# DAC_GainOutputStage.net
KiCad netlist of a schematic drawn in EAGLE
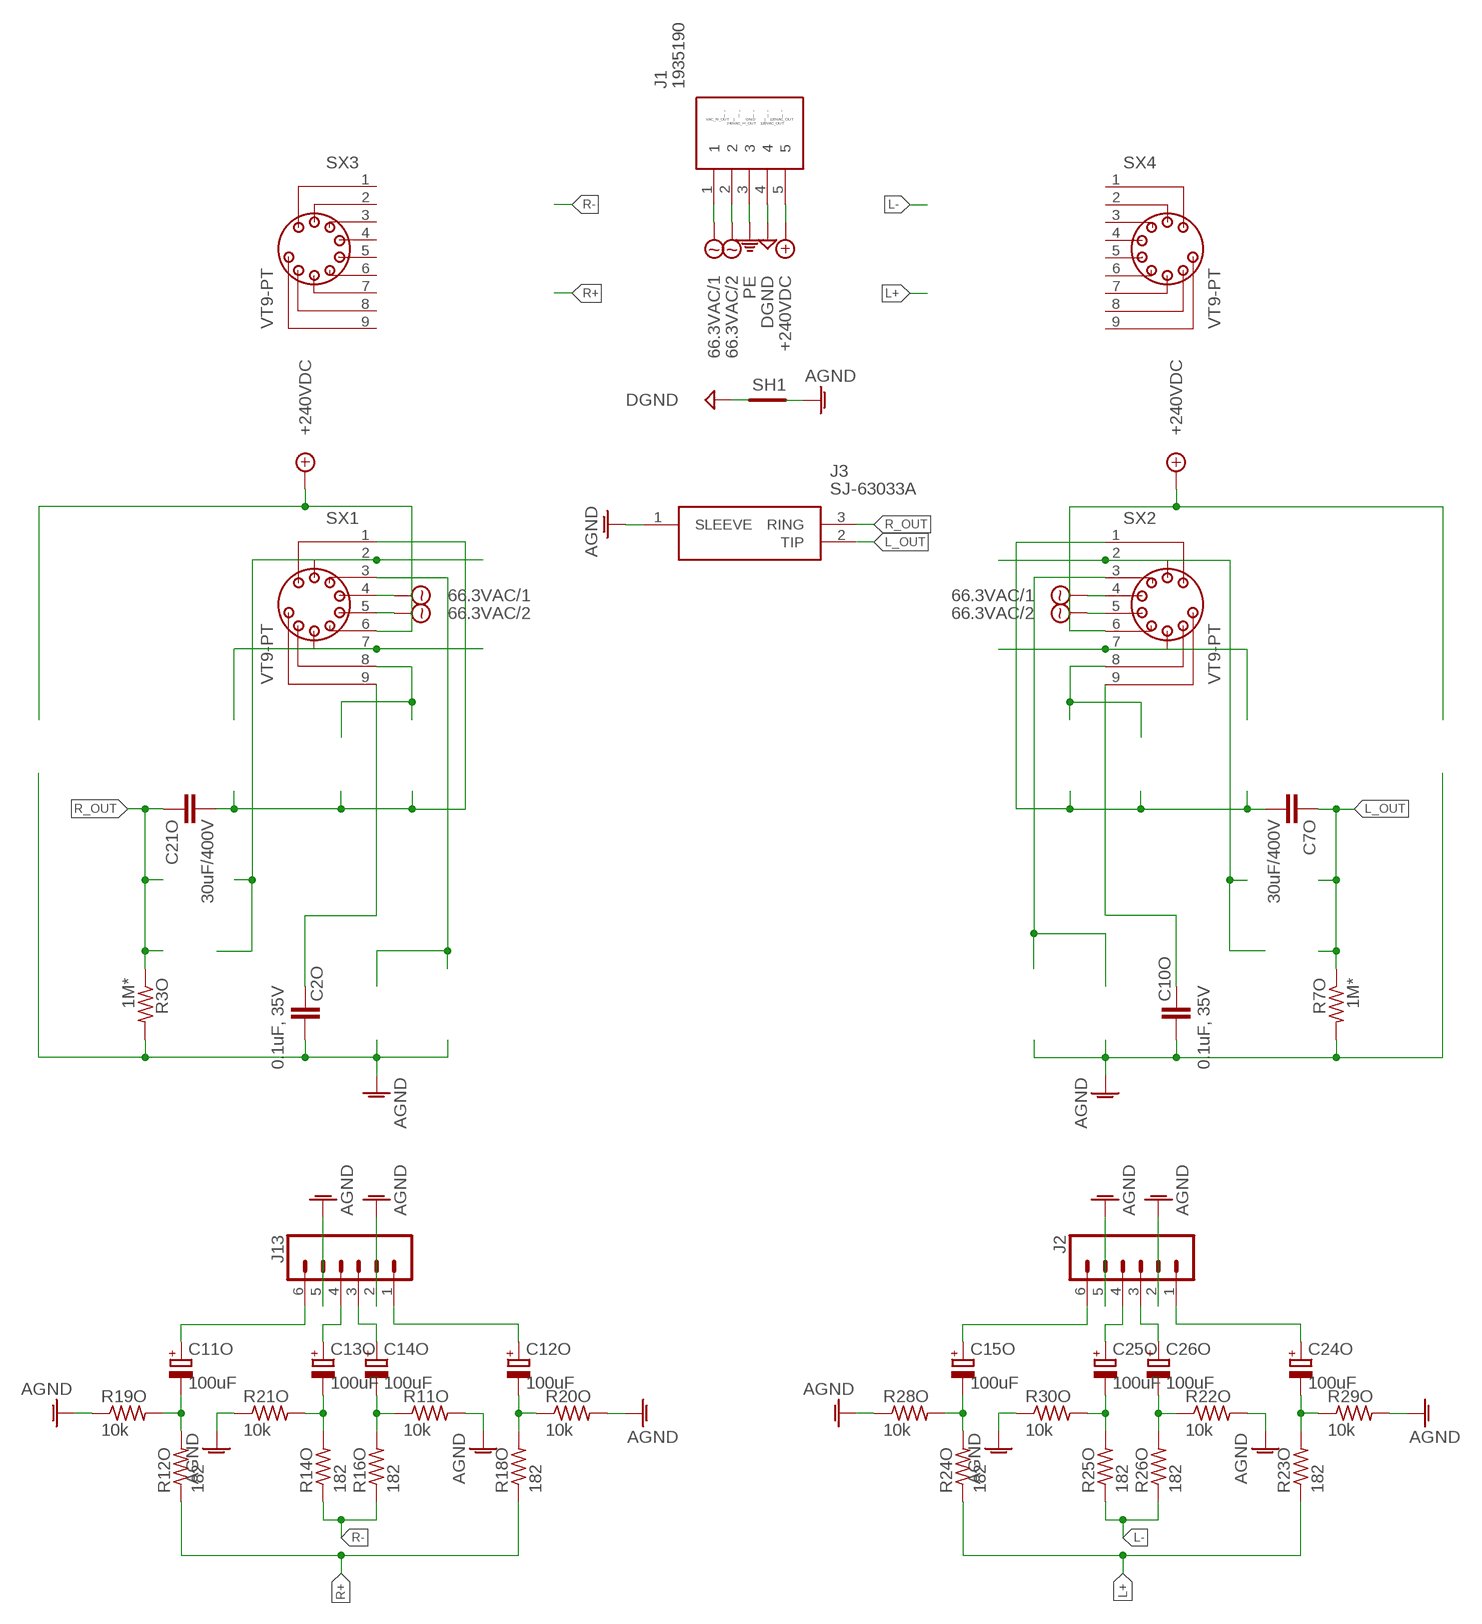
[diagram p0: schematic, sheet 1]

(export (version "E")
  (design (tool "Eeschema 10.0.6"))
  (components
    (comp (ref "C2O")
      (value "0.1uF, 35V")
      (footprint "eagle-import:MKS4B031002A00JC00")
      (fields
        (field (name "MANUFACTURER_PART_NUMBER") "MKS4B031002A00JC00")
        (field (name "MOUSER_PART_NUMBER") "505-MKS4B0312AJC")
      )
      (libsource (lib "eagle-import") (part "MKS4B031002A00JC00"))
    )
    (comp (ref "C7O")
      (value "30uF/400V")
      (footprint "eagle-import:DCP4G053006ID2KSSD")
      (fields
        (field (name "MANUFACTURER_PART_NUMBER") "DCP4G053006ID2KSSD")
        (field (name "MOUSER_PART_NUMBER") "505-DCP4G0536ID2KSSD")
      )
      (libsource (lib "eagle-import") (part "DCP4G053006ID2KSSD"))
    )
    (comp (ref "C10O")
      (value "0.1uF, 35V")
      (footprint "eagle-import:MKS4B031002A00JC00")
      (fields
        (field (name "MANUFACTURER_PART_NUMBER") "MKS4B031002A00JC00")
        (field (name "MOUSER_PART_NUMBER") "505-MKS4B0312AJC")
      )
      (libsource (lib "eagle-import") (part "MKS4B031002A00JC00"))
    )
    (comp (ref "C11O")
      (value "100uF")
      (footprint "eagle-import:CAPPRD350W60D825H1300")
      (fields
        (field (name "ARROW_PART_NUMBER") "UFW1H101MPD1TD")
        (field (name "MOUSER_PART_NUMBER") "647-UFW1H101MPD1TD")
      )
      (libsource (lib "eagle-import") (part "UFW1H101MPD1TD"))
    )
    (comp (ref "C12O")
      (value "100uF")
      (footprint "eagle-import:CAPPRD350W60D825H1300")
      (fields
        (field (name "ARROW_PART_NUMBER") "UFW1H101MPD1TD")
        (field (name "MOUSER_PART_NUMBER") "647-UFW1H101MPD1TD")
      )
      (libsource (lib "eagle-import") (part "UFW1H101MPD1TD"))
    )
    (comp (ref "C13O")
      (value "100uF")
      (footprint "eagle-import:CAPPRD350W60D825H1300")
      (fields
        (field (name "ARROW_PART_NUMBER") "UFW1H101MPD1TD")
        (field (name "MOUSER_PART_NUMBER") "647-UFW1H101MPD1TD")
      )
      (libsource (lib "eagle-import") (part "UFW1H101MPD1TD"))
    )
    (comp (ref "C14O")
      (value "100uF")
      (footprint "eagle-import:CAPPRD350W60D825H1300")
      (fields
        (field (name "ARROW_PART_NUMBER") "UFW1H101MPD1TD")
        (field (name "MOUSER_PART_NUMBER") "647-UFW1H101MPD1TD")
      )
      (libsource (lib "eagle-import") (part "UFW1H101MPD1TD"))
    )
    (comp (ref "C15O")
      (value "100uF")
      (footprint "eagle-import:CAPPRD350W60D825H1300")
      (fields
        (field (name "ARROW_PART_NUMBER") "UFW1H101MPD1TD")
        (field (name "MOUSER_PART_NUMBER") "647-UFW1H101MPD1TD")
      )
      (libsource (lib "eagle-import") (part "UFW1H101MPD1TD"))
    )
    (comp (ref "C21O")
      (value "30uF/400V")
      (footprint "eagle-import:DCP4G053006ID2KSSD")
      (fields
        (field (name "MANUFACTURER_PART_NUMBER") "DCP4G053006ID2KSSD")
        (field (name "MOUSER_PART_NUMBER") "505-DCP4G0536ID2KSSD")
      )
      (libsource (lib "eagle-import") (part "DCP4G053006ID2KSSD"))
    )
    (comp (ref "C24O")
      (value "100uF")
      (footprint "eagle-import:CAPPRD350W60D825H1300")
      (fields
        (field (name "ARROW_PART_NUMBER") "UFW1H101MPD1TD")
        (field (name "MOUSER_PART_NUMBER") "647-UFW1H101MPD1TD")
      )
      (libsource (lib "eagle-import") (part "UFW1H101MPD1TD"))
    )
    (comp (ref "C25O")
      (value "100uF")
      (footprint "eagle-import:CAPPRD350W60D825H1300")
      (fields
        (field (name "ARROW_PART_NUMBER") "UFW1H101MPD1TD")
        (field (name "MOUSER_PART_NUMBER") "647-UFW1H101MPD1TD")
      )
      (libsource (lib "eagle-import") (part "UFW1H101MPD1TD"))
    )
    (comp (ref "C26O")
      (value "100uF")
      (footprint "eagle-import:CAPPRD350W60D825H1300")
      (fields
        (field (name "ARROW_PART_NUMBER") "UFW1H101MPD1TD")
        (field (name "MOUSER_PART_NUMBER") "647-UFW1H101MPD1TD")
      )
      (libsource (lib "eagle-import") (part "UFW1H101MPD1TD"))
    )
    (comp (ref "J1")
      (value "1935190")
      (footprint "eagle-import:1935190")
      (fields (field (name "MOUSER_PART_NUMBER") "651-1935190"))
      (libsource (lib "eagle-import") (part "1935190"))
    )
    (comp (ref "J2")
      (value "CONN_06SILK_FEMALE_PTH")
      (footprint "eagle-import:1X06")
      (libsource (lib "eagle-import") (part "CONN_06SILK_FEMALE_PTH"))
    )
    (comp (ref "J3")
      (value "SJ-63033A")
      (footprint "eagle-import:SJ63033A")
      (libsource (lib "eagle-import") (part "SJ-63033A"))
    )
    (comp (ref "J13")
      (value "CONN_06SILK_FEMALE_PTH")
      (footprint "eagle-import:1X06")
      (libsource (lib "eagle-import") (part "CONN_06SILK_FEMALE_PTH"))
    )
    (comp (ref "R3O")
      (value "1M*")
      (footprint "eagle-import:RESAD1540W60L620D230")
      (fields
        (field (name "MANUFACTURER_PART_NUMBER") "LR1F1M0")
        (field (name "MOUSER_PART_NUMBER") "279-LR1F1M0")
      )
      (libsource (lib "eagle-import") (part "LR1F1M0"))
    )
    (comp (ref "R7O")
      (value "1M*")
      (footprint "eagle-import:RESAD1540W60L620D230")
      (fields
        (field (name "MANUFACTURER_PART_NUMBER") "LR1F1M0")
        (field (name "MOUSER_PART_NUMBER") "279-LR1F1M0")
      )
      (libsource (lib "eagle-import") (part "LR1F1M0"))
    )
    (comp (ref "R11O")
      (value "10k")
      (footprint "eagle-import:RESAD1540W55L620D230")
      (fields
        (field (name "MANUFACTURER_PART_NUMBER") "LR1F10K")
        (field (name "MOUSER_PART_NUMBER") "279-LR1F10K")
      )
      (libsource (lib "eagle-import") (part "LR1F10K"))
    )
    (comp (ref "R12O")
      (value "182")
      (footprint "eagle-import:RESAD1590W60L630D240")
      (fields (field (name "MANUFACTURER_PART_NUMBER") "MF0207FTE52-182R"))
      (libsource (lib "eagle-import") (part "MF0207FTE52-182R"))
    )
    (comp (ref "R14O")
      (value "182")
      (footprint "eagle-import:RESAD1590W60L630D240")
      (fields (field (name "MANUFACTURER_PART_NUMBER") "MF0207FTE52-182R"))
      (libsource (lib "eagle-import") (part "MF0207FTE52-182R"))
    )
    (comp (ref "R16O")
      (value "182")
      (footprint "eagle-import:RESAD1590W60L630D240")
      (fields (field (name "MANUFACTURER_PART_NUMBER") "MF0207FTE52-182R"))
      (libsource (lib "eagle-import") (part "MF0207FTE52-182R"))
    )
    (comp (ref "R18O")
      (value "182")
      (footprint "eagle-import:RESAD1590W60L630D240")
      (fields (field (name "MANUFACTURER_PART_NUMBER") "MF0207FTE52-182R"))
      (libsource (lib "eagle-import") (part "MF0207FTE52-182R"))
    )
    (comp (ref "R19O")
      (value "10k")
      (footprint "eagle-import:RESAD1540W55L620D230")
      (fields
        (field (name "MANUFACTURER_PART_NUMBER") "LR1F10K")
        (field (name "MOUSER_PART_NUMBER") "279-LR1F10K")
      )
      (libsource (lib "eagle-import") (part "LR1F10K"))
    )
    (comp (ref "R20O")
      (value "10k")
      (footprint "eagle-import:RESAD1540W55L620D230")
      (fields
        (field (name "MANUFACTURER_PART_NUMBER") "LR1F10K")
        (field (name "MOUSER_PART_NUMBER") "279-LR1F10K")
      )
      (libsource (lib "eagle-import") (part "LR1F10K"))
    )
    (comp (ref "R21O")
      (value "10k")
      (footprint "eagle-import:RESAD1540W55L620D230")
      (fields
        (field (name "MANUFACTURER_PART_NUMBER") "LR1F10K")
        (field (name "MOUSER_PART_NUMBER") "279-LR1F10K")
      )
      (libsource (lib "eagle-import") (part "LR1F10K"))
    )
    (comp (ref "R22O")
      (value "10k")
      (footprint "eagle-import:RESAD1540W55L620D230")
      (fields
        (field (name "MANUFACTURER_PART_NUMBER") "LR1F10K")
        (field (name "MOUSER_PART_NUMBER") "279-LR1F10K")
      )
      (libsource (lib "eagle-import") (part "LR1F10K"))
    )
    (comp (ref "R23O")
      (value "182")
      (footprint "eagle-import:RESAD1590W60L630D240")
      (fields (field (name "MANUFACTURER_PART_NUMBER") "MF0207FTE52-182R"))
      (libsource (lib "eagle-import") (part "MF0207FTE52-182R"))
    )
    (comp (ref "R24O")
      (value "182")
      (footprint "eagle-import:RESAD1590W60L630D240")
      (fields (field (name "MANUFACTURER_PART_NUMBER") "MF0207FTE52-182R"))
      (libsource (lib "eagle-import") (part "MF0207FTE52-182R"))
    )
    (comp (ref "R25O")
      (value "182")
      (footprint "eagle-import:RESAD1590W60L630D240")
      (fields (field (name "MANUFACTURER_PART_NUMBER") "MF0207FTE52-182R"))
      (libsource (lib "eagle-import") (part "MF0207FTE52-182R"))
    )
    (comp (ref "R26O")
      (value "182")
      (footprint "eagle-import:RESAD1590W60L630D240")
      (fields (field (name "MANUFACTURER_PART_NUMBER") "MF0207FTE52-182R"))
      (libsource (lib "eagle-import") (part "MF0207FTE52-182R"))
    )
    (comp (ref "R28O")
      (value "10k")
      (footprint "eagle-import:RESAD1540W55L620D230")
      (fields
        (field (name "MANUFACTURER_PART_NUMBER") "LR1F10K")
        (field (name "MOUSER_PART_NUMBER") "279-LR1F10K")
      )
      (libsource (lib "eagle-import") (part "LR1F10K"))
    )
    (comp (ref "R29O")
      (value "10k")
      (footprint "eagle-import:RESAD1540W55L620D230")
      (fields
        (field (name "MANUFACTURER_PART_NUMBER") "LR1F10K")
        (field (name "MOUSER_PART_NUMBER") "279-LR1F10K")
      )
      (libsource (lib "eagle-import") (part "LR1F10K"))
    )
    (comp (ref "R30O")
      (value "10k")
      (footprint "eagle-import:RESAD1540W55L620D230")
      (fields
        (field (name "MANUFACTURER_PART_NUMBER") "LR1F10K")
        (field (name "MOUSER_PART_NUMBER") "279-LR1F10K")
      )
      (libsource (lib "eagle-import") (part "LR1F10K"))
    )
    (comp (ref "SH1")
      (value "SHORTA5")
      (footprint "eagle-import:SHORT_ALL-50")
      (libsource (lib "eagle-import") (part "SHORTA5"))
    )
    (comp (ref "SX1")
      (value "VT9-PT")
      (footprint "eagle-import:VT9-PT")
      (libsource (lib "eagle-import") (part "VT9-PT"))
    )
    (comp (ref "SX2")
      (value "VT9-PT")
      (footprint "eagle-import:VT9-PT")
      (libsource (lib "eagle-import") (part "VT9-PT"))
    )
    (comp (ref "SX3")
      (value "VT9-PT")
      (footprint "eagle-import:VT9-PT")
      (libsource (lib "eagle-import") (part "VT9-PT"))
    )
    (comp (ref "SX4")
      (value "VT9-PT")
      (footprint "eagle-import:VT9-PT")
      (libsource (lib "eagle-import") (part "VT9-PT"))
    )
  )
  (nets
    (net (code "1") (name "+240VDC") (class "Default")
      (node (ref "J1") (pin "5") (pinfunction "5_5") (pintype "bidirectional"))
      (node (ref "SX1") (pin "6") (pinfunction "6_6") (pintype "passive"))
      (node (ref "SX2") (pin "6") (pinfunction "6_6") (pintype "passive"))
    )
    (net (code "2") (name "66.3VAC{slash}1") (class "Default")
      (node (ref "J1") (pin "1") (pinfunction "1_1") (pintype "bidirectional"))
      (node (ref "SX1") (pin "4") (pinfunction "4_4") (pintype "passive"))
      (node (ref "SX2") (pin "4") (pinfunction "4_4") (pintype "passive"))
    )
    (net (code "3") (name "66.3VAC{slash}2") (class "Default")
      (node (ref "J1") (pin "2") (pinfunction "2_2") (pintype "bidirectional"))
      (node (ref "SX1") (pin "5") (pinfunction "5_5") (pintype "passive"))
      (node (ref "SX2") (pin "5") (pinfunction "5_5") (pintype "passive"))
    )
    (net (code "4") (name "AGND") (class "Default")
      (node (ref "C10O") (pin "2") (pinfunction "2_2") (pintype "passive"))
      (node (ref "C2O") (pin "2") (pinfunction "2_2") (pintype "passive"))
      (node (ref "J13") (pin "2") (pinfunction "2_2") (pintype "passive"))
      (node (ref "J13") (pin "5") (pinfunction "5_5") (pintype "passive"))
      (node (ref "J2") (pin "2") (pinfunction "2_2") (pintype "passive"))
      (node (ref "J2") (pin "5") (pinfunction "5_5") (pintype "passive"))
      (node (ref "J3") (pin "1") (pinfunction "SLEEVE_1") (pintype "bidirectional"))
      (node (ref "R11O") (pin "2") (pinfunction "2_2") (pintype "passive"))
      (node (ref "R19O") (pin "1") (pinfunction "1_1") (pintype "passive"))
      (node (ref "R20O") (pin "2") (pinfunction "2_2") (pintype "passive"))
      (node (ref "R21O") (pin "1") (pinfunction "1_1") (pintype "passive"))
      (node (ref "R22O") (pin "2") (pinfunction "2_2") (pintype "passive"))
      (node (ref "R28O") (pin "1") (pinfunction "1_1") (pintype "passive"))
      (node (ref "R29O") (pin "2") (pinfunction "2_2") (pintype "passive"))
      (node (ref "R30O") (pin "1") (pinfunction "1_1") (pintype "passive"))
      (node (ref "R3O") (pin "2") (pinfunction "2_2") (pintype "passive"))
      (node (ref "R7O") (pin "2") (pinfunction "2_2") (pintype "passive"))
      (node (ref "SH1") (pin "2") (pinfunction "P$2_2") (pintype "bidirectional"))
    )
    (net (code "5") (name "DGND") (class "Default")
      (node (ref "J1") (pin "4") (pinfunction "4_4") (pintype "bidirectional"))
      (node (ref "SH1") (pin "1") (pinfunction "P$1_1") (pintype "bidirectional"))
    )
    (net (code "6") (name "L+") (class "Default")
      (node (ref "R23O") (pin "1") (pinfunction "1_1") (pintype "passive"))
      (node (ref "R24O") (pin "1") (pinfunction "1_1") (pintype "passive"))
    )
    (net (code "7") (name "L-") (class "Default")
      (node (ref "R25O") (pin "1") (pinfunction "1_1") (pintype "passive"))
      (node (ref "R26O") (pin "1") (pinfunction "1_1") (pintype "passive"))
    )
    (net (code "8") (name "L_OUT") (class "Default")
      (node (ref "C7O") (pin "1") (pinfunction "1_1") (pintype "passive"))
      (node (ref "J3") (pin "2") (pinfunction "TIP_2") (pintype "bidirectional"))
      (node (ref "R7O") (pin "1") (pinfunction "1_1") (pintype "passive"))
    )
    (net (code "9") (name "Net-(C2O-Pad1)") (class "Default")
      (node (ref "C2O") (pin "1") (pinfunction "1_1") (pintype "passive"))
      (node (ref "SX1") (pin "9") (pinfunction "9_9") (pintype "passive"))
    )
    (net (code "10") (name "Net-(C7O-Pad2)") (class "Default")
      (node (ref "C7O") (pin "2") (pinfunction "2_2") (pintype "passive"))
      (node (ref "SX2") (pin "1") (pinfunction "1_1") (pintype "passive"))
    )
    (net (code "11") (name "Net-(C10O-Pad1)") (class "Default")
      (node (ref "C10O") (pin "1") (pinfunction "1_1") (pintype "passive"))
      (node (ref "SX2") (pin "9") (pinfunction "9_9") (pintype "passive"))
    )
    (net (code "12") (name "Net-(C11O-+)") (class "Default")
      (node (ref "C11O") (pin "1") (pinfunction "+_1") (pintype "passive"))
      (node (ref "J13") (pin "6") (pinfunction "6_6") (pintype "passive"))
    )
    (net (code "13") (name "Net-(C11O--)") (class "Default")
      (node (ref "C11O") (pin "2") (pinfunction "-_2") (pintype "passive"))
      (node (ref "R12O") (pin "2") (pinfunction "2_2") (pintype "passive"))
      (node (ref "R19O") (pin "2") (pinfunction "2_2") (pintype "passive"))
    )
    (net (code "14") (name "Net-(C12O-+)") (class "Default")
      (node (ref "C12O") (pin "1") (pinfunction "+_1") (pintype "passive"))
      (node (ref "J13") (pin "1") (pinfunction "1_1") (pintype "passive"))
    )
    (net (code "15") (name "Net-(C12O--)") (class "Default")
      (node (ref "C12O") (pin "2") (pinfunction "-_2") (pintype "passive"))
      (node (ref "R18O") (pin "2") (pinfunction "2_2") (pintype "passive"))
      (node (ref "R20O") (pin "1") (pinfunction "1_1") (pintype "passive"))
    )
    (net (code "16") (name "Net-(C13O-+)") (class "Default")
      (node (ref "C13O") (pin "1") (pinfunction "+_1") (pintype "passive"))
      (node (ref "J13") (pin "4") (pinfunction "4_4") (pintype "passive"))
    )
    (net (code "17") (name "Net-(C13O--)") (class "Default")
      (node (ref "C13O") (pin "2") (pinfunction "-_2") (pintype "passive"))
      (node (ref "R14O") (pin "2") (pinfunction "2_2") (pintype "passive"))
      (node (ref "R21O") (pin "2") (pinfunction "2_2") (pintype "passive"))
    )
    (net (code "18") (name "Net-(C14O-+)") (class "Default")
      (node (ref "C14O") (pin "1") (pinfunction "+_1") (pintype "passive"))
      (node (ref "J13") (pin "3") (pinfunction "3_3") (pintype "passive"))
    )
    (net (code "19") (name "Net-(C14O--)") (class "Default")
      (node (ref "C14O") (pin "2") (pinfunction "-_2") (pintype "passive"))
      (node (ref "R11O") (pin "1") (pinfunction "1_1") (pintype "passive"))
      (node (ref "R16O") (pin "2") (pinfunction "2_2") (pintype "passive"))
    )
    (net (code "20") (name "Net-(C15O-+)") (class "Default")
      (node (ref "C15O") (pin "1") (pinfunction "+_1") (pintype "passive"))
      (node (ref "J2") (pin "6") (pinfunction "6_6") (pintype "passive"))
    )
    (net (code "21") (name "Net-(C15O--)") (class "Default")
      (node (ref "C15O") (pin "2") (pinfunction "-_2") (pintype "passive"))
      (node (ref "R24O") (pin "2") (pinfunction "2_2") (pintype "passive"))
      (node (ref "R28O") (pin "2") (pinfunction "2_2") (pintype "passive"))
    )
    (net (code "22") (name "Net-(C21O-Pad2)") (class "Default")
      (node (ref "C21O") (pin "2") (pinfunction "2_2") (pintype "passive"))
      (node (ref "SX1") (pin "1") (pinfunction "1_1") (pintype "passive"))
    )
    (net (code "23") (name "Net-(C24O-+)") (class "Default")
      (node (ref "C24O") (pin "1") (pinfunction "+_1") (pintype "passive"))
      (node (ref "J2") (pin "1") (pinfunction "1_1") (pintype "passive"))
    )
    (net (code "24") (name "Net-(C24O--)") (class "Default")
      (node (ref "C24O") (pin "2") (pinfunction "-_2") (pintype "passive"))
      (node (ref "R23O") (pin "2") (pinfunction "2_2") (pintype "passive"))
      (node (ref "R29O") (pin "1") (pinfunction "1_1") (pintype "passive"))
    )
    (net (code "25") (name "Net-(C25O-+)") (class "Default")
      (node (ref "C25O") (pin "1") (pinfunction "+_1") (pintype "passive"))
      (node (ref "J2") (pin "4") (pinfunction "4_4") (pintype "passive"))
    )
    (net (code "26") (name "Net-(C25O--)") (class "Default")
      (node (ref "C25O") (pin "2") (pinfunction "-_2") (pintype "passive"))
      (node (ref "R25O") (pin "2") (pinfunction "2_2") (pintype "passive"))
      (node (ref "R30O") (pin "2") (pinfunction "2_2") (pintype "passive"))
    )
    (net (code "27") (name "Net-(C26O-+)") (class "Default")
      (node (ref "C26O") (pin "1") (pinfunction "+_1") (pintype "passive"))
      (node (ref "J2") (pin "3") (pinfunction "3_3") (pintype "passive"))
    )
    (net (code "28") (name "Net-(C26O--)") (class "Default")
      (node (ref "C26O") (pin "2") (pinfunction "-_2") (pintype "passive"))
      (node (ref "R22O") (pin "1") (pinfunction "1_1") (pintype "passive"))
      (node (ref "R26O") (pin "2") (pinfunction "2_2") (pintype "passive"))
    )
    (net (code "29") (name "PE") (class "Default")
      (node (ref "J1") (pin "3") (pinfunction "3_3") (pintype "bidirectional"))
    )
    (net (code "30") (name "R+") (class "Default")
      (node (ref "R12O") (pin "1") (pinfunction "1_1") (pintype "passive"))
      (node (ref "R18O") (pin "1") (pinfunction "1_1") (pintype "passive"))
    )
    (net (code "31") (name "R-") (class "Default")
      (node (ref "R14O") (pin "1") (pinfunction "1_1") (pintype "passive"))
      (node (ref "R16O") (pin "1") (pinfunction "1_1") (pintype "passive"))
    )
    (net (code "32") (name "R_OUT") (class "Default")
      (node (ref "C21O") (pin "1") (pinfunction "1_1") (pintype "passive"))
      (node (ref "J3") (pin "3") (pinfunction "RING_3") (pintype "bidirectional"))
      (node (ref "R3O") (pin "1") (pinfunction "1_1") (pintype "passive"))
    )
    (net (code "33") (name "unconnected-(SX1-Pad2)") (class "Default")
      (node (ref "SX1") (pin "2") (pinfunction "2_2") (pintype "passive"))
    )
    (net (code "34") (name "unconnected-(SX1-Pad3)") (class "Default")
      (node (ref "SX1") (pin "3") (pinfunction "3_3") (pintype "passive"))
    )
    (net (code "35") (name "unconnected-(SX1-Pad7)") (class "Default")
      (node (ref "SX1") (pin "7") (pinfunction "7_7") (pintype "passive"))
    )
    (net (code "36") (name "unconnected-(SX1-Pad8)") (class "Default")
      (node (ref "SX1") (pin "8") (pinfunction "8_8") (pintype "passive"))
    )
    (net (code "37") (name "unconnected-(SX2-Pad2)") (class "Default")
      (node (ref "SX2") (pin "2") (pinfunction "2_2") (pintype "passive"))
    )
    (net (code "38") (name "unconnected-(SX2-Pad3)") (class "Default")
      (node (ref "SX2") (pin "3") (pinfunction "3_3") (pintype "passive"))
    )
    (net (code "39") (name "unconnected-(SX2-Pad7)") (class "Default")
      (node (ref "SX2") (pin "7") (pinfunction "7_7") (pintype "passive"))
    )
    (net (code "40") (name "unconnected-(SX2-Pad8)") (class "Default")
      (node (ref "SX2") (pin "8") (pinfunction "8_8") (pintype "passive"))
    )
    (net (code "41") (name "unconnected-(SX3-Pad1)") (class "Default")
      (node (ref "SX3") (pin "1") (pinfunction "1_1") (pintype "passive"))
    )
    (net (code "42") (name "unconnected-(SX3-Pad2)") (class "Default")
      (node (ref "SX3") (pin "2") (pinfunction "2_2") (pintype "passive"))
    )
    (net (code "43") (name "unconnected-(SX3-Pad3)") (class "Default")
      (node (ref "SX3") (pin "3") (pinfunction "3_3") (pintype "passive"))
    )
    (net (code "44") (name "unconnected-(SX3-Pad4)") (class "Default")
      (node (ref "SX3") (pin "4") (pinfunction "4_4") (pintype "passive"))
    )
    (net (code "45") (name "unconnected-(SX3-Pad5)") (class "Default")
      (node (ref "SX3") (pin "5") (pinfunction "5_5") (pintype "passive"))
    )
    (net (code "46") (name "unconnected-(SX3-Pad6)") (class "Default")
      (node (ref "SX3") (pin "6") (pinfunction "6_6") (pintype "passive"))
    )
    (net (code "47") (name "unconnected-(SX3-Pad7)") (class "Default")
      (node (ref "SX3") (pin "7") (pinfunction "7_7") (pintype "passive"))
    )
    (net (code "48") (name "unconnected-(SX3-Pad8)") (class "Default")
      (node (ref "SX3") (pin "8") (pinfunction "8_8") (pintype "passive"))
    )
    (net (code "49") (name "unconnected-(SX3-Pad9)") (class "Default")
      (node (ref "SX3") (pin "9") (pinfunction "9_9") (pintype "passive"))
    )
    (net (code "50") (name "unconnected-(SX4-Pad1)") (class "Default")
      (node (ref "SX4") (pin "1") (pinfunction "1_1") (pintype "passive"))
    )
    (net (code "51") (name "unconnected-(SX4-Pad2)") (class "Default")
      (node (ref "SX4") (pin "2") (pinfunction "2_2") (pintype "passive"))
    )
    (net (code "52") (name "unconnected-(SX4-Pad3)") (class "Default")
      (node (ref "SX4") (pin "3") (pinfunction "3_3") (pintype "passive"))
    )
    (net (code "53") (name "unconnected-(SX4-Pad4)") (class "Default")
      (node (ref "SX4") (pin "4") (pinfunction "4_4") (pintype "passive"))
    )
    (net (code "54") (name "unconnected-(SX4-Pad5)") (class "Default")
      (node (ref "SX4") (pin "5") (pinfunction "5_5") (pintype "passive"))
    )
    (net (code "55") (name "unconnected-(SX4-Pad6)") (class "Default")
      (node (ref "SX4") (pin "6") (pinfunction "6_6") (pintype "passive"))
    )
    (net (code "56") (name "unconnected-(SX4-Pad7)") (class "Default")
      (node (ref "SX4") (pin "7") (pinfunction "7_7") (pintype "passive"))
    )
    (net (code "57") (name "unconnected-(SX4-Pad8)") (class "Default")
      (node (ref "SX4") (pin "8") (pinfunction "8_8") (pintype "passive"))
    )
    (net (code "58") (name "unconnected-(SX4-Pad9)") (class "Default")
      (node (ref "SX4") (pin "9") (pinfunction "9_9") (pintype "passive"))
    )
  )
)
